# LED.net
KiCad netlist of a schematic drawn in Altium Designer
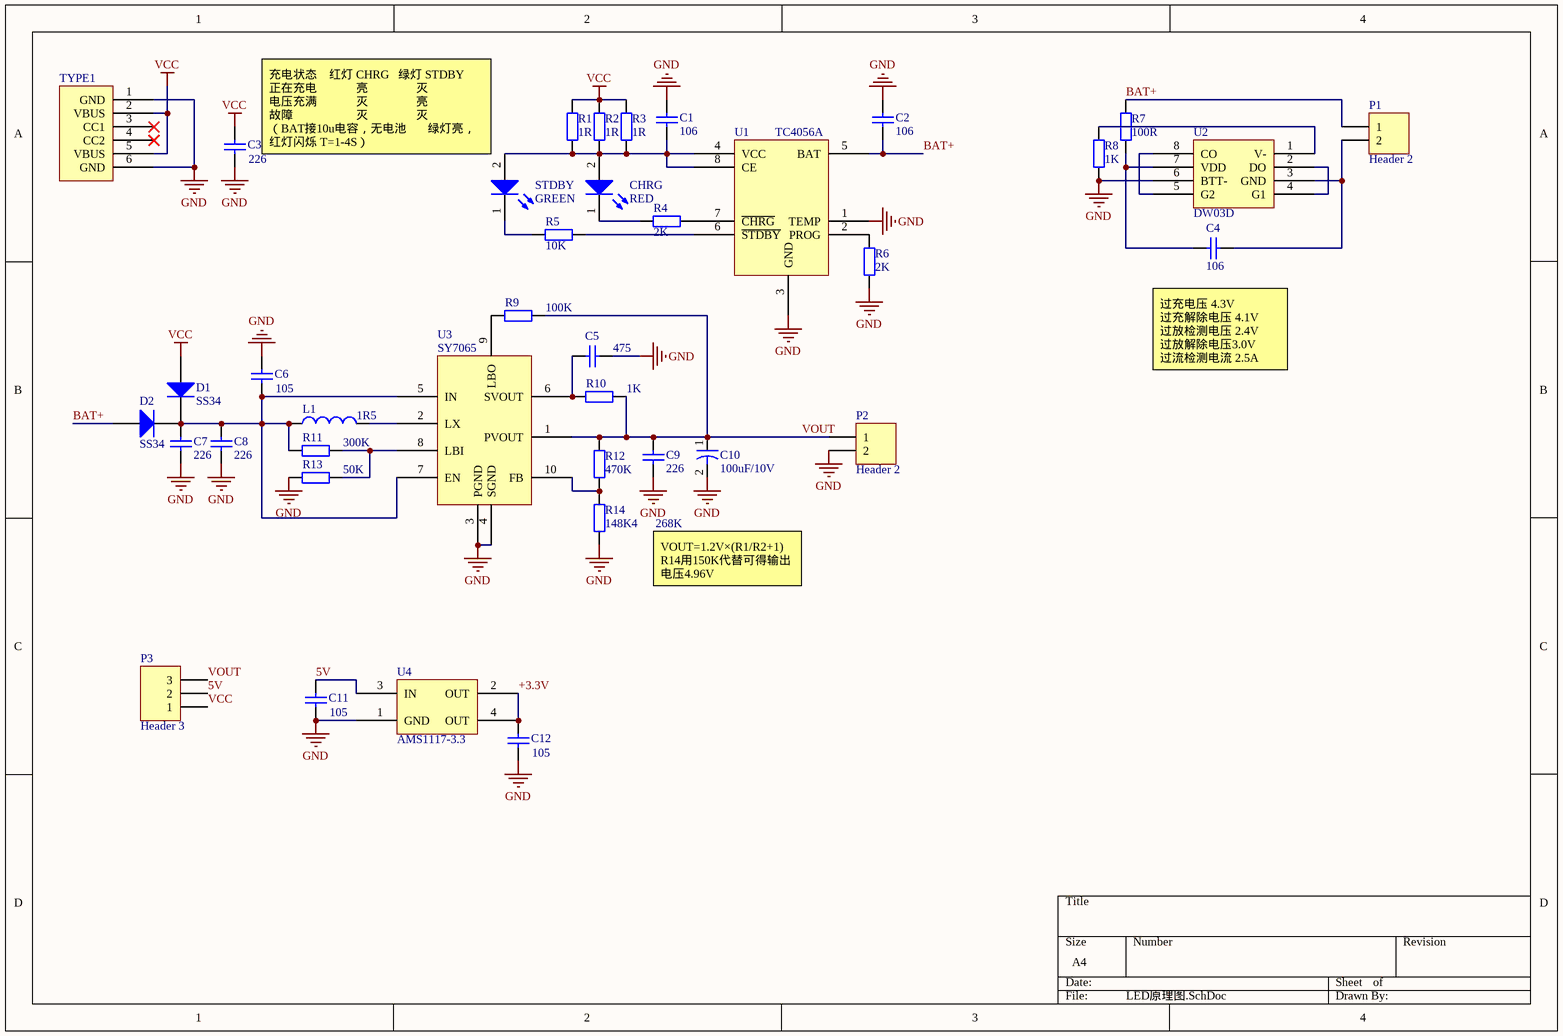
[diagram p0: LED原理图.SchDoc]

(export (version "E")
  (design (tool "Eeschema 10.0.6"))
  (components
    (comp (ref "C1")
      (value "106")
      (footprint "0805C")
      (description "Capacitor")
      (fields (field (name "Comment") "Cap") (field (name "PUBLISHER") "Altium Limited"))
      (libsource (lib "Miscellaneous Devices") (part "Cap"))
    )
    (comp (ref "C2")
      (value "106")
      (footprint "0805C")
      (description "Capacitor")
      (fields (field (name "Comment") "Cap") (field (name "PUBLISHER") "Altium Limited"))
      (libsource (lib "Miscellaneous Devices") (part "Cap"))
    )
    (comp (ref "C3")
      (value "226")
      (footprint "0805C")
      (description "Capacitor")
      (fields (field (name "Comment") "Cap") (field (name "PUBLISHER") "Altium Limited"))
      (libsource (lib "Miscellaneous Devices") (part "Cap"))
    )
    (comp (ref "C4")
      (value "106")
      (footprint "0805C")
      (description "Capacitor")
      (fields (field (name "Comment") "Cap") (field (name "PUBLISHER") "Altium Limited"))
      (libsource (lib "Miscellaneous Devices") (part "Cap"))
    )
    (comp (ref "C5")
      (value "475")
      (footprint "0805C")
      (description "Capacitor")
      (fields (field (name "Comment") "Cap") (field (name "PUBLISHER") "Altium Limited"))
      (libsource (lib "Miscellaneous Devices") (part "Cap"))
    )
    (comp (ref "C6")
      (value "105")
      (footprint "0805C")
      (description "Capacitor")
      (fields (field (name "Comment") "Cap") (field (name "PUBLISHER") "Altium Limited"))
      (libsource (lib "Miscellaneous Devices") (part "Cap"))
    )
    (comp (ref "C7")
      (value "226")
      (footprint "0805C")
      (description "Capacitor")
      (fields (field (name "Comment") "Cap") (field (name "PUBLISHER") "Altium Limited"))
      (libsource (lib "Miscellaneous Devices") (part "Cap"))
    )
    (comp (ref "C8")
      (value "226")
      (footprint "0805C")
      (description "Capacitor")
      (fields (field (name "Comment") "Cap") (field (name "PUBLISHER") "Altium Limited"))
      (libsource (lib "Miscellaneous Devices") (part "Cap"))
    )
    (comp (ref "C9")
      (value "226")
      (footprint "0805C")
      (description "Capacitor")
      (fields (field (name "Comment") "Cap") (field (name "PUBLISHER") "Altium Limited"))
      (libsource (lib "Miscellaneous Devices") (part "Cap"))
    )
    (comp (ref "C10")
      (value "100uF/10V")
      (footprint "贴片电容:C1206")
      (description "Capacitor")
      (fields (field (name "Comment") "Cap2") (field (name "PUBLISHER") "Altium Limited"))
      (libsource (lib "Miscellaneous Devices") (part "Cap2"))
    )
    (comp (ref "C11")
      (value "105")
      (footprint "0805C")
      (description "Capacitor")
      (fields (field (name "Comment") "Cap") (field (name "PUBLISHER") "Altium Limited"))
      (libsource (lib "Miscellaneous Devices") (part "Cap"))
    )
    (comp (ref "C12")
      (value "105")
      (footprint "0805C")
      (description "Capacitor")
      (fields (field (name "Comment") "Cap") (field (name "PUBLISHER") "Altium Limited"))
      (libsource (lib "Miscellaneous Devices") (part "Cap"))
    )
    (comp (ref "CHRG")
      (value "RED")
      (footprint "LED-0805")
      (description "Typical INFRARED GaAs LED")
      (fields (field (name "PUBLISHER") "Altium Limited"))
      (libsource (lib "Miscellaneous Devices") (part "LED0"))
    )
    (comp (ref "D1")
      (value "SS34")
      (footprint "LC-SMA(DO-214AC)_S2")
      (description "Default Diode")
      (fields (field (name "PUBLISHER") "Altium Limited"))
      (libsource (lib "Miscellaneous Devices") (part "Diode"))
    )
    (comp (ref "D2")
      (value "SS34")
      (footprint "LC-SMA(DO-214AC)_S2")
      (description "Default Diode")
      (fields (field (name "PUBLISHER") "Altium Limited"))
      (libsource (lib "Miscellaneous Devices") (part "Diode"))
    )
    (comp (ref "L1")
      (value "1R5")
      (footprint "电感SMD")
      (description "Inductor")
      (fields (field (name "PUBLISHER") "Altium Limited"))
      (libsource (lib "Miscellaneous Devices") (part "Inductor"))
    )
    (comp (ref "P1")
      (value "Header 2")
      (footprint "XH2.54-2")
      (description "Header, 2-Pin")
      (fields (field (name "PUBLISHER") "Altium Limited"))
      (libsource (lib "Miscellaneous Connectors") (part "Header 2"))
    )
    (comp (ref "P2")
      (value "Header 2")
      (footprint "XH2.54-2")
      (description "Header, 2-Pin")
      (fields (field (name "PUBLISHER") "Altium Limited"))
      (libsource (lib "Miscellaneous Connectors") (part "Header 2"))
    )
    (comp (ref "P3")
      (value "Header 3")
      (footprint "XH2.54-3")
      (description "Header, 3-Pin")
      (fields (field (name "PUBLISHER") "Altium Limited"))
      (libsource (lib "Miscellaneous Connectors") (part "Header 3"))
    )
    (comp (ref "R1")
      (value "1R")
      (footprint "0805R")
      (description "Resistor")
      (fields (field (name "Comment") "Res2") (field (name "PUBLISHER") "Altium Limited"))
      (libsource (lib "") (part "Res2_2"))
    )
    (comp (ref "R2")
      (value "1R")
      (footprint "0805R")
      (description "Resistor")
      (fields (field (name "Comment") "Res2") (field (name "PUBLISHER") "Altium Limited"))
      (libsource (lib "") (part "Res2_2"))
    )
    (comp (ref "R3")
      (value "1R")
      (footprint "0805R")
      (description "Resistor")
      (fields (field (name "Comment") "Res2") (field (name "PUBLISHER") "Altium Limited"))
      (libsource (lib "") (part "Res2_2"))
    )
    (comp (ref "R4")
      (value "2K")
      (footprint "0805R")
      (description "Resistor")
      (fields (field (name "Comment") "Res2") (field (name "PUBLISHER") "Altium Limited"))
      (libsource (lib "Miscellaneous Devices") (part "Res2"))
    )
    (comp (ref "R5")
      (value "10K")
      (footprint "0805R")
      (description "Resistor")
      (fields (field (name "Comment") "Res2") (field (name "PUBLISHER") "Altium Limited"))
      (libsource (lib "Miscellaneous Devices") (part "Res2"))
    )
    (comp (ref "R6")
      (value "2K")
      (footprint "0805R")
      (description "Resistor")
      (fields (field (name "Comment") "Res2") (field (name "PUBLISHER") "Altium Limited"))
      (libsource (lib "") (part "Res2_1"))
    )
    (comp (ref "R7")
      (value "100R")
      (footprint "0805R")
      (description "Resistor")
      (fields (field (name "Comment") "Res2") (field (name "PUBLISHER") "Altium Limited"))
      (libsource (lib "") (part "Res2_2"))
    )
    (comp (ref "R8")
      (value "1K")
      (footprint "0805R")
      (description "Resistor")
      (fields (field (name "Comment") "Res2") (field (name "PUBLISHER") "Altium Limited"))
      (libsource (lib "") (part "Res2_2"))
    )
    (comp (ref "R9")
      (value "100K")
      (footprint "0805R")
      (description "Resistor")
      (fields (field (name "Comment") "Res2") (field (name "PUBLISHER") "Altium Limited"))
      (libsource (lib "Miscellaneous Devices") (part "Res2"))
    )
    (comp (ref "R10")
      (value "1K")
      (footprint "0805R")
      (description "Resistor")
      (fields (field (name "Comment") "Res2") (field (name "PUBLISHER") "Altium Limited"))
      (libsource (lib "Miscellaneous Devices") (part "Res2"))
    )
    (comp (ref "R11")
      (value "300K")
      (footprint "0805R")
      (description "Resistor")
      (fields (field (name "Comment") "Res2") (field (name "PUBLISHER") "Altium Limited"))
      (libsource (lib "Miscellaneous Devices") (part "Res2"))
    )
    (comp (ref "R12")
      (value "470K")
      (footprint "0805R")
      (description "Resistor")
      (fields (field (name "Comment") "Res2") (field (name "PUBLISHER") "Altium Limited"))
      (libsource (lib "") (part "Res2_1"))
    )
    (comp (ref "R13")
      (value "50K")
      (footprint "0805R")
      (description "Resistor")
      (fields (field (name "Comment") "Res2") (field (name "PUBLISHER") "Altium Limited"))
      (libsource (lib "Miscellaneous Devices") (part "Res2"))
    )
    (comp (ref "R14")
      (value "148K4      268K")
      (footprint "0805R")
      (description "Resistor")
      (fields (field (name "Comment") "Res2") (field (name "PUBLISHER") "Altium Limited"))
      (libsource (lib "") (part "Res2_1"))
    )
    (comp (ref "STDBY")
      (value "GREEN")
      (footprint "LED-0805")
      (description "Typical INFRARED GaAs LED")
      (fields (field (name "PUBLISHER") "Altium Limited"))
      (libsource (lib "Miscellaneous Devices") (part "LED0"))
    )
    (comp (ref "TYPE1")
      (value "TYPE-CF-6P-RAT-L6.8W")
      (footprint "TYPE-CF-6P-RAT-L6.8W")
      (libsource (lib "原理图库") (part "TYPE-CF-6P-RAT-L6.8W"))
    )
    (comp (ref "U1") (value "TC4056A") (footprint "SOP-8") (libsource (lib "原理图库") (part "TC4056A")))
    (comp (ref "U2")
      (value "DW03D")
      (footprint "LC-TSSOP-8_3x4.4x065P")
      (libsource (lib "原理图库") (part "DW03D"))
    )
    (comp (ref "U3") (value "SY7065") (footprint "QFN2*2-10") (libsource (lib "原理图库") (part "SY7065")))
    (comp (ref "U4")
      (value "AMS1117-3.3")
      (footprint "SOT-233")
      (libsource (lib "原理图库") (part "AMS1117-3.3"))
    )
  )
  (nets
    (net (code "1") (name "/+3.3V") (class "Default")
      (node (ref "C12") (pin "2") (pinfunction "2_2") (pintype "passive"))
      (node (ref "U4") (pin "2") (pinfunction "OUT_2") (pintype "passive"))
      (node (ref "U4") (pin "4") (pinfunction "OUT_4") (pintype "passive"))
    )
    (net (code "2") (name "/5V") (class "Default")
      (node (ref "C11") (pin "2") (pinfunction "2_2") (pintype "passive"))
      (node (ref "P3") (pin "2") (pinfunction "2_2") (pintype "passive"))
      (node (ref "U4") (pin "3") (pinfunction "IN_3") (pintype "passive"))
    )
    (net (code "3") (name "/BAT+") (class "Default")
      (node (ref "C2") (pin "1") (pinfunction "1_1") (pintype "passive"))
      (node (ref "D2") (pin "1") (pinfunction "A_1") (pintype "passive"))
      (node (ref "P1") (pin "1") (pinfunction "1_1") (pintype "passive"))
      (node (ref "R7") (pin "1") (pinfunction "1_1") (pintype "passive"))
      (node (ref "U1") (pin "5") (pinfunction "BAT_5") (pintype "passive"))
    )
    (net (code "4") (name "/VOUT") (class "Default")
      (node (ref "C10") (pin "1") (pinfunction "1_1") (pintype "passive"))
      (node (ref "C9") (pin "1") (pinfunction "1_1") (pintype "passive"))
      (node (ref "P2") (pin "1") (pinfunction "1_1") (pintype "passive"))
      (node (ref "P3") (pin "3") (pinfunction "3_3") (pintype "passive"))
      (node (ref "R10") (pin "2") (pinfunction "2_2") (pintype "passive"))
      (node (ref "R12") (pin "2") (pinfunction "2_2") (pintype "passive"))
      (node (ref "R9") (pin "2") (pinfunction "2_2") (pintype "passive"))
      (node (ref "U3") (pin "1") (pinfunction "PVOUT_1") (pintype "passive"))
    )
    (net (code "5") (name "GND") (class "Default")
      (node (ref "C1") (pin "2") (pinfunction "2_2") (pintype "passive"))
      (node (ref "C10") (pin "2") (pinfunction "2_2") (pintype "passive"))
      (node (ref "C11") (pin "1") (pinfunction "1_1") (pintype "passive"))
      (node (ref "C12") (pin "1") (pinfunction "1_1") (pintype "passive"))
      (node (ref "C2") (pin "2") (pinfunction "2_2") (pintype "passive"))
      (node (ref "C3") (pin "1") (pinfunction "1_1") (pintype "passive"))
      (node (ref "C5") (pin "1") (pinfunction "1_1") (pintype "passive"))
      (node (ref "C6") (pin "2") (pinfunction "2_2") (pintype "passive"))
      (node (ref "C7") (pin "1") (pinfunction "1_1") (pintype "passive"))
      (node (ref "C8") (pin "1") (pinfunction "1_1") (pintype "passive"))
      (node (ref "C9") (pin "2") (pinfunction "2_2") (pintype "passive"))
      (node (ref "P2") (pin "2") (pinfunction "2_2") (pintype "passive"))
      (node (ref "R13") (pin "1") (pinfunction "1_1") (pintype "passive"))
      (node (ref "R14") (pin "1") (pinfunction "1_1") (pintype "passive"))
      (node (ref "R6") (pin "1") (pinfunction "1_1") (pintype "passive"))
      (node (ref "R8") (pin "2") (pinfunction "2_2") (pintype "passive"))
      (node (ref "TYPE1") (pin "1") (pinfunction "GND_1") (pintype "passive"))
      (node (ref "TYPE1") (pin "6") (pinfunction "GND_6") (pintype "passive"))
      (node (ref "U1") (pin "1") (pinfunction "TEMP_1") (pintype "passive"))
      (node (ref "U1") (pin "3") (pinfunction "GND_3") (pintype "passive"))
      (node (ref "U2") (pin "6") (pinfunction "BTT-_6") (pintype "passive"))
      (node (ref "U3") (pin "3") (pinfunction "PGND_3") (pintype "passive"))
      (node (ref "U3") (pin "4") (pinfunction "SGND_4") (pintype "passive"))
      (node (ref "U4") (pin "1") (pinfunction "GND_1") (pintype "passive"))
    )
    (net (code "6") (name "Net-(CHRG-A)") (class "Default")
      (node (ref "C1") (pin "1") (pinfunction "1_1") (pintype "passive"))
      (node (ref "CHRG") (pin "2") (pinfunction "A_2") (pintype "passive"))
      (node (ref "R1") (pin "2") (pinfunction "2_2") (pintype "passive"))
      (node (ref "R2") (pin "2") (pinfunction "2_2") (pintype "passive"))
      (node (ref "R3") (pin "2") (pinfunction "2_2") (pintype "passive"))
      (node (ref "STDBY") (pin "2") (pinfunction "A_2") (pintype "passive"))
      (node (ref "U1") (pin "4") (pinfunction "VCC_4") (pintype "passive"))
      (node (ref "U1") (pin "8") (pinfunction "CE_8") (pintype "passive"))
    )
    (net (code "7") (name "Net-(CHRG-K)") (class "Default")
      (node (ref "CHRG") (pin "1") (pinfunction "K_1") (pintype "passive"))
      (node (ref "R4") (pin "1") (pinfunction "1_1") (pintype "passive"))
    )
    (net (code "8") (name "Net-(D1-K)") (class "Default")
      (node (ref "C6") (pin "1") (pinfunction "1_1") (pintype "passive"))
      (node (ref "C7") (pin "2") (pinfunction "2_2") (pintype "passive"))
      (node (ref "C8") (pin "2") (pinfunction "2_2") (pintype "passive"))
      (node (ref "D1") (pin "2") (pinfunction "K_2") (pintype "passive"))
      (node (ref "D2") (pin "2") (pinfunction "K_2") (pintype "passive"))
      (node (ref "L1") (pin "1") (pinfunction "1_1") (pintype "passive"))
      (node (ref "R11") (pin "1") (pinfunction "1_1") (pintype "passive"))
      (node (ref "U3") (pin "5") (pinfunction "IN_5") (pintype "passive"))
      (node (ref "U3") (pin "7") (pinfunction "EN_7") (pintype "passive"))
    )
    (net (code "9") (name "Net-(STDBY-K)") (class "Default")
      (node (ref "R5") (pin "1") (pinfunction "1_1") (pintype "passive"))
      (node (ref "STDBY") (pin "1") (pinfunction "K_1") (pintype "passive"))
    )
    (net (code "10") (name "Net-(U1-PROG)") (class "Default")
      (node (ref "R6") (pin "2") (pinfunction "2_2") (pintype "passive"))
      (node (ref "U1") (pin "2") (pinfunction "PROG_2") (pintype "passive"))
    )
    (net (code "11") (name "Net-(U1-~{CHRG})") (class "Default")
      (node (ref "R4") (pin "2") (pinfunction "2_2") (pintype "passive"))
      (node (ref "U1") (pin "7") (pinfunction "~{CHRG}_7") (pintype "passive"))
    )
    (net (code "12") (name "Net-(U1-~{STDBY})") (class "Default")
      (node (ref "R5") (pin "2") (pinfunction "2_2") (pintype "passive"))
      (node (ref "U1") (pin "6") (pinfunction "~{STDBY}_6") (pintype "passive"))
    )
    (net (code "13") (name "Net-(U2-CO)") (class "Default")
      (node (ref "U2") (pin "5") (pinfunction "G2_5") (pintype "passive"))
      (node (ref "U2") (pin "8") (pinfunction "CO_8") (pintype "passive"))
    )
    (net (code "14") (name "Net-(U2-DO)") (class "Default")
      (node (ref "U2") (pin "2") (pinfunction "DO_2") (pintype "passive"))
      (node (ref "U2") (pin "4") (pinfunction "G1_4") (pintype "passive"))
    )
    (net (code "15") (name "Net-(U2-GND)") (class "Default")
      (node (ref "C4") (pin "1") (pinfunction "1_1") (pintype "passive"))
      (node (ref "P1") (pin "2") (pinfunction "2_2") (pintype "passive"))
      (node (ref "U2") (pin "3") (pinfunction "GND_3") (pintype "passive"))
    )
    (net (code "16") (name "Net-(U2-V-)") (class "Default")
      (node (ref "R8") (pin "1") (pinfunction "1_1") (pintype "passive"))
      (node (ref "U2") (pin "1") (pinfunction "V-_1") (pintype "passive"))
    )
    (net (code "17") (name "Net-(U2-VDD)") (class "Default")
      (node (ref "C4") (pin "2") (pinfunction "2_2") (pintype "passive"))
      (node (ref "R7") (pin "2") (pinfunction "2_2") (pintype "passive"))
      (node (ref "U2") (pin "7") (pinfunction "VDD_7") (pintype "passive"))
    )
    (net (code "18") (name "Net-(U3-FB)") (class "Default")
      (node (ref "R12") (pin "1") (pinfunction "1_1") (pintype "passive"))
      (node (ref "R14") (pin "2") (pinfunction "2_2") (pintype "passive"))
      (node (ref "U3") (pin "10") (pinfunction "FB_10") (pintype "passive"))
    )
    (net (code "19") (name "Net-(U3-LBI)") (class "Default")
      (node (ref "R11") (pin "2") (pinfunction "2_2") (pintype "passive"))
      (node (ref "R13") (pin "2") (pinfunction "2_2") (pintype "passive"))
      (node (ref "U3") (pin "8") (pinfunction "LBI_8") (pintype "passive"))
    )
    (net (code "20") (name "Net-(U3-LBO)") (class "Default")
      (node (ref "R9") (pin "1") (pinfunction "1_1") (pintype "passive"))
      (node (ref "U3") (pin "9") (pinfunction "LBO_9") (pintype "passive"))
    )
    (net (code "21") (name "Net-(U3-LX)") (class "Default")
      (node (ref "L1") (pin "2") (pinfunction "2_2") (pintype "passive"))
      (node (ref "U3") (pin "2") (pinfunction "LX_2") (pintype "passive"))
    )
    (net (code "22") (name "Net-(U3-SVOUT)") (class "Default")
      (node (ref "C5") (pin "2") (pinfunction "2_2") (pintype "passive"))
      (node (ref "R10") (pin "1") (pinfunction "1_1") (pintype "passive"))
      (node (ref "U3") (pin "6") (pinfunction "SVOUT_6") (pintype "passive"))
    )
    (net (code "23") (name "VCC") (class "Default")
      (node (ref "C3") (pin "2") (pinfunction "2_2") (pintype "passive"))
      (node (ref "D1") (pin "1") (pinfunction "A_1") (pintype "passive"))
      (node (ref "P3") (pin "1") (pinfunction "1_1") (pintype "passive"))
      (node (ref "R1") (pin "1") (pinfunction "1_1") (pintype "passive"))
      (node (ref "R2") (pin "1") (pinfunction "1_1") (pintype "passive"))
      (node (ref "R3") (pin "1") (pinfunction "1_1") (pintype "passive"))
      (node (ref "TYPE1") (pin "2") (pinfunction "VBUS_2") (pintype "passive"))
      (node (ref "TYPE1") (pin "5") (pinfunction "VBUS_5") (pintype "passive"))
    )
    (net (code "24") (name "unconnected-(TYPE1-CC1-Pad3)") (class "Default")
      (node (ref "TYPE1") (pin "3") (pinfunction "CC1_3") (pintype "passive+no_connect"))
    )
    (net (code "25") (name "unconnected-(TYPE1-CC2-Pad4)") (class "Default")
      (node (ref "TYPE1") (pin "4") (pinfunction "CC2_4") (pintype "passive+no_connect"))
    )
  )
)
